# APM_BLE.net
KiCad netlist of a schematic drawn in EAGLE
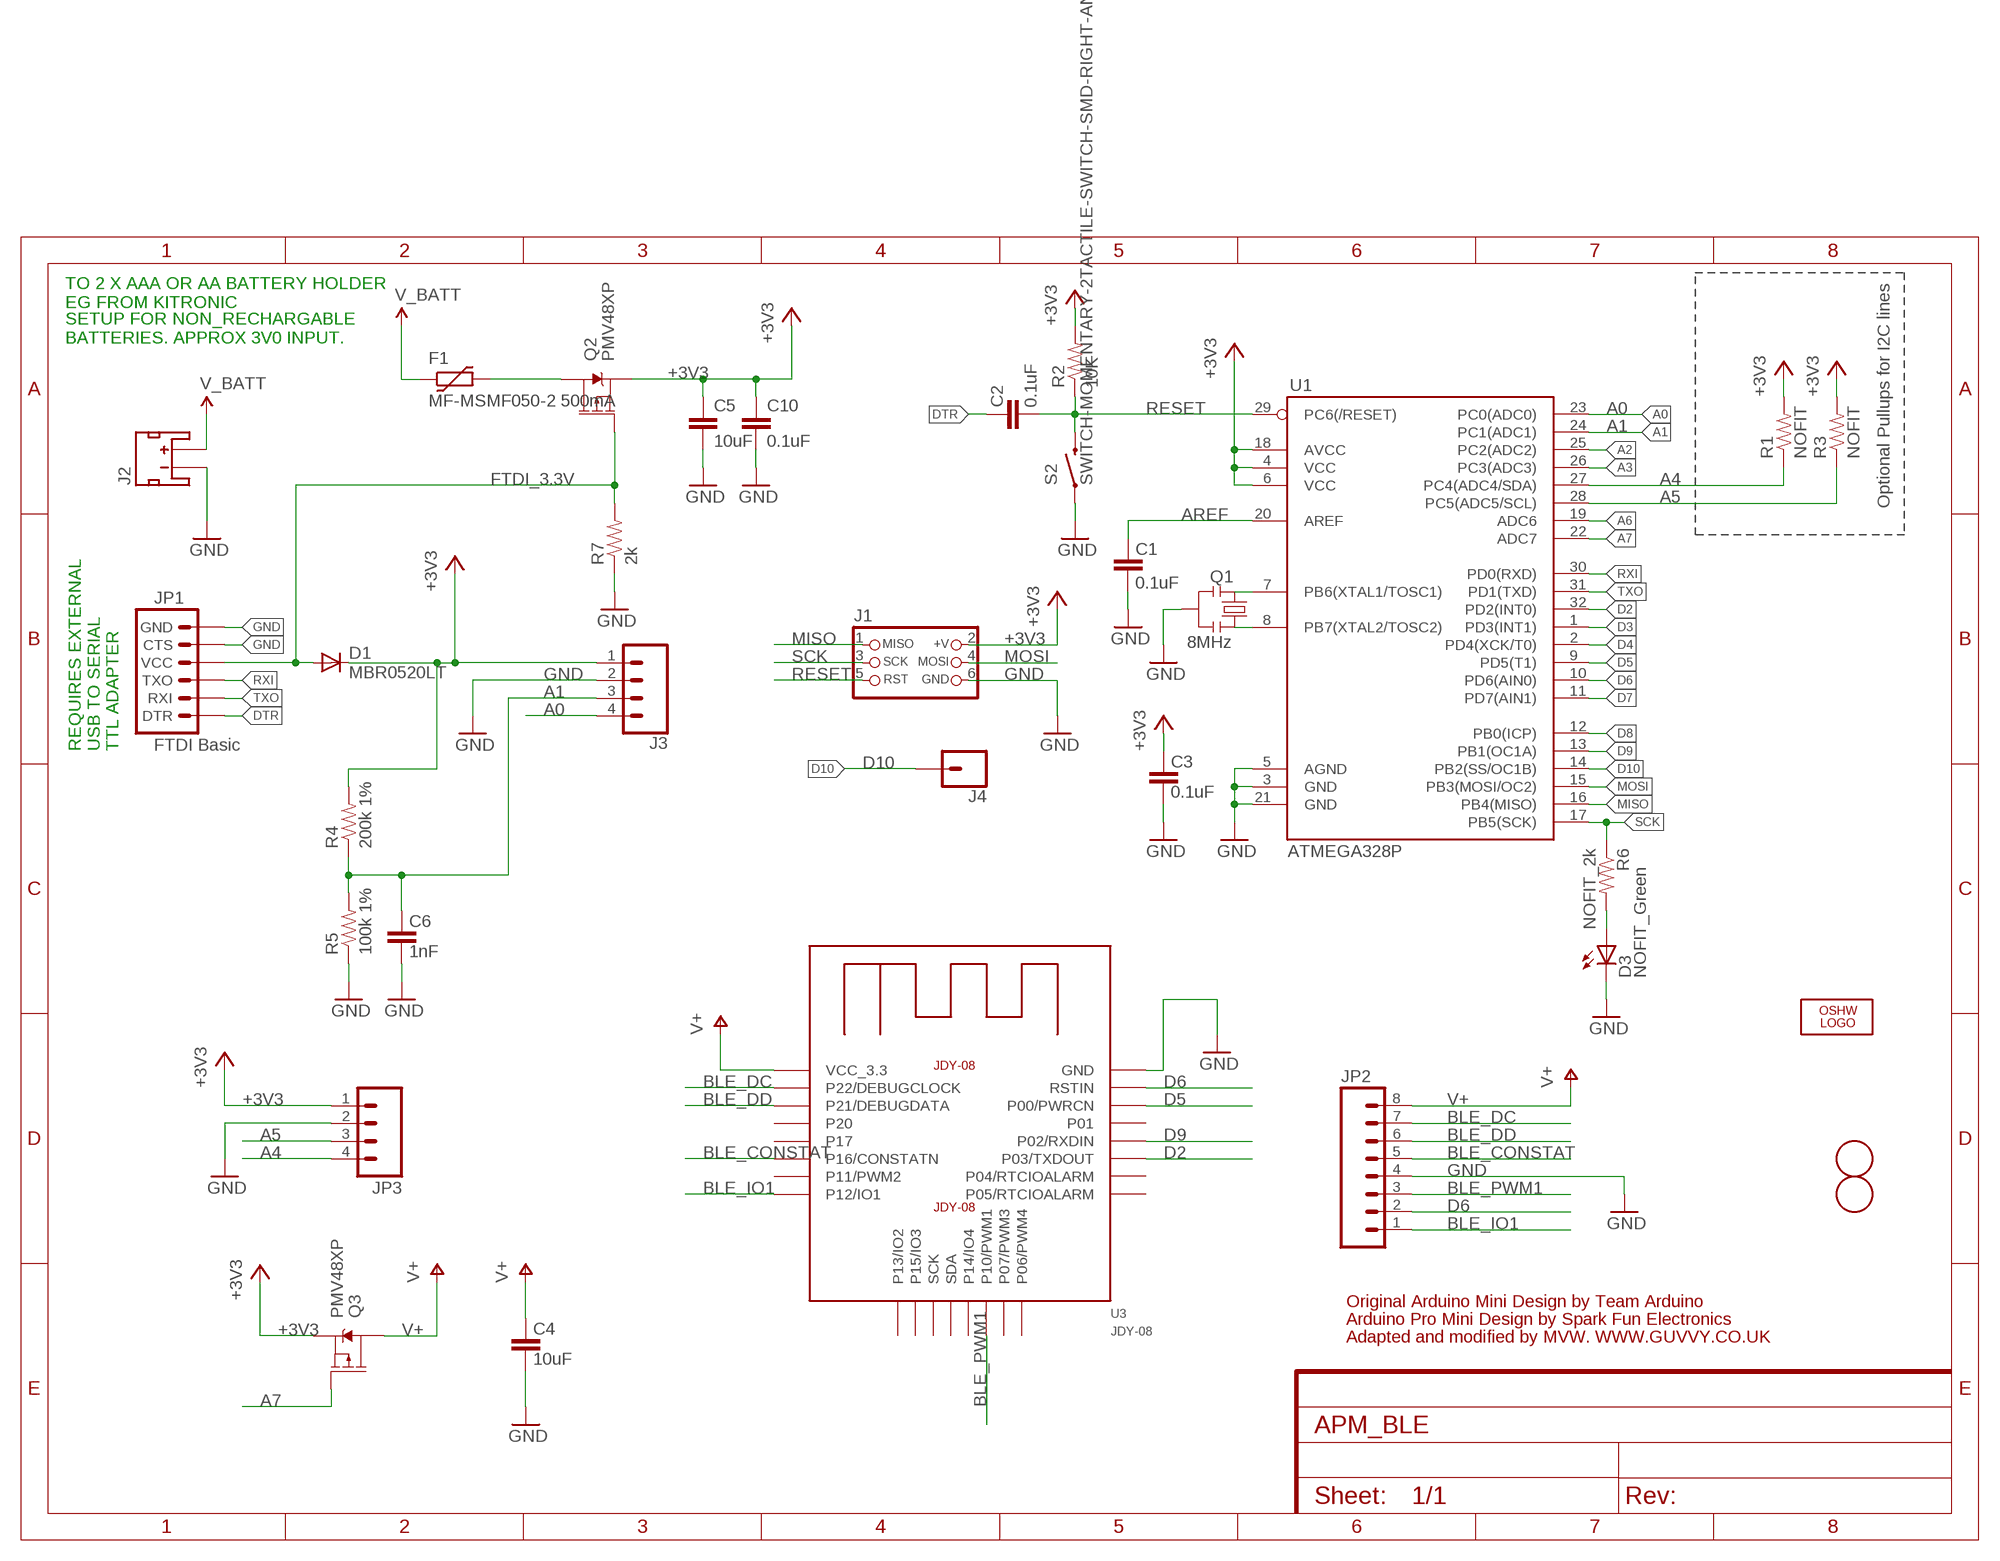
[diagram p0: schematic, sheet 1]

(export (version "E")
  (design (tool "Eeschema 10.0.6"))
  (components
    (comp (ref "C1")
      (value "0.1uF")
      (footprint "eagle-import:0603-CAP")
      (libsource (lib "eagle-import") (part "CAP0603-CAP"))
    )
    (comp (ref "C2")
      (value "0.1uF")
      (footprint "eagle-import:0603-CAP")
      (libsource (lib "eagle-import") (part "CAP0603-CAP"))
    )
    (comp (ref "C3")
      (value "0.1uF")
      (footprint "eagle-import:0603-CAP")
      (libsource (lib "eagle-import") (part "CAP0603-CAP"))
    )
    (comp (ref "C4")
      (value "10uF")
      (footprint "eagle-import:0603-CAP")
      (libsource (lib "eagle-import") (part "CAP0603-CAP"))
    )
    (comp (ref "C5")
      (value "10uF")
      (footprint "eagle-import:C0805K")
      (libsource (lib "eagle-import") (part "C-EUC0805K"))
    )
    (comp (ref "C6")
      (value "1nF")
      (footprint "eagle-import:0603-CAP")
      (libsource (lib "eagle-import") (part "CAP0603-CAP"))
    )
    (comp (ref "C10")
      (value "0.1uF")
      (footprint "eagle-import:0603-CAP")
      (libsource (lib "eagle-import") (part "CAP0603-CAP"))
    )
    (comp (ref "D1")
      (value "MBR0520LT")
      (footprint "eagle-import:SOD123")
      (libsource (lib "eagle-import") (part "MBR0520LT"))
    )
    (comp (ref "D3")
      (value "NOFIT_Green")
      (footprint "eagle-import:0603-LED-ALT1")
      (libsource (lib "eagle-import") (part "LED"))
    )
    (comp (ref "F1")
      (value "MF-MSMF050-2 500mA")
      (footprint "eagle-import:PTC1812L")
      (libsource (lib "eagle-import") (part "FUSE_PTC-1812"))
    )
    (comp (ref "FID1")
      (value "FIDUCIAL")
      (footprint "eagle-import:FIDUCIAL_1MM")
      (libsource (lib "eagle-import") (part "FIDUCIAL"))
    )
    (comp (ref "FID2")
      (value "FIDUCIAL")
      (footprint "eagle-import:FIDUCIAL_1MM")
      (libsource (lib "eagle-import") (part "FIDUCIAL"))
    )
    (comp (ref "J1")
      (value "CON_HEADER_PRG_AVR_ICSP-PTH")
      (footprint "eagle-import:HEADER_PRG_2X03")
      (libsource (lib "eagle-import") (part "CON_HEADER_PRG_AVR_ICSP-PTH"))
    )
    (comp (ref "J2")
      (value "B2B-PH-K-S(LF)(SN)")
      (footprint "eagle-import:JST-2-SMD")
      (libsource (lib "eagle-import") (part "JST_2MM_MALE"))
    )
    (comp (ref "J3")
      (value "CONN_04")
      (footprint "eagle-import:1X04")
      (libsource (lib "eagle-import") (part "CONN_04"))
    )
    (comp (ref "J4")
      (value "CONN_01")
      (footprint "eagle-import:1X01")
      (libsource (lib "eagle-import") (part "CONN_01"))
    )
    (comp (ref "JP1")
      (value "FTDI Basic")
      (footprint "eagle-import:1X06")
      (libsource (lib "eagle-import") (part "ARDUINO_SERIAL_PROGRAMPTH"))
    )
    (comp (ref "JP2")
      (value "M08BM08B-SRSS-TB")
      (footprint "eagle-import:BM08B-SRSS-TB")
      (libsource (lib "eagle-import") (part "M08BM08B-SRSS-TB"))
    )
    (comp (ref "JP3")
      (value "M04PTH")
      (footprint "eagle-import:1X04")
      (libsource (lib "eagle-import") (part "M04PTH"))
    )
    (comp (ref "LOGO1")
      (value "OSHW_LOGO_FILLX0200-NT")
      (footprint "eagle-import:OSHW_FILLX200_NOTEXT")
      (libsource (lib "eagle-import") (part "OSHW_LOGO_FILLX0200-NT"))
    )
    (comp (ref "Q1")
      (value "8MHz")
      (footprint "eagle-import:RESONATOR-SMD-1_1")
      (libsource (lib "eagle-import") (part "RESONATOR1{colon}1"))
    )
    (comp (ref "Q2")
      (value "PMV48XP")
      (footprint "eagle-import:SOT23-3")
      (libsource (lib "eagle-import") (part "MOSFET_PCH-IRLML2244"))
    )
    (comp (ref "Q3")
      (value "PMV48XP")
      (footprint "eagle-import:SOT23-3")
      (libsource (lib "eagle-import") (part "MOSFET_PCH-IRLML2244"))
    )
    (comp (ref "R1")
      (value "NOFIT")
      (footprint "eagle-import:0603-RES")
      (libsource (lib "eagle-import") (part "RESISTOR0603-RES"))
    )
    (comp (ref "R2")
      (value "10K")
      (footprint "eagle-import:0603-RES")
      (libsource (lib "eagle-import") (part "RESISTOR0603-RES"))
    )
    (comp (ref "R3")
      (value "NOFIT")
      (footprint "eagle-import:0603-RES")
      (libsource (lib "eagle-import") (part "RESISTOR0603-RES"))
    )
    (comp (ref "R4")
      (value "200k 1%")
      (footprint "eagle-import:0603-RES")
      (libsource (lib "eagle-import") (part "RESISTOR0603-RES"))
    )
    (comp (ref "R5")
      (value "100k 1%")
      (footprint "eagle-import:0603-RES")
      (libsource (lib "eagle-import") (part "RESISTOR0603-RES"))
    )
    (comp (ref "R6")
      (value "NOFIT_2k")
      (footprint "eagle-import:0603-RES")
      (libsource (lib "eagle-import") (part "RESISTOR0603-RES"))
    )
    (comp (ref "R7")
      (value "2k")
      (footprint "eagle-import:0603-RES")
      (libsource (lib "eagle-import") (part "RESISTOR0603-RES"))
    )
    (comp (ref "S2")
      (value "SWITCH-MOMENTARY-2TACTILE-SWITCH-SMD-RIGHT-ANGLE")
      (footprint "eagle-import:TACTILE_SWITCH-SMD-RIGHT-ANGLE")
      (libsource (lib "eagle-import") (part "SWITCH-MOMENTARY-2TACTILE-SWITCH-SMD-RIGHT-ANGLE"))
    )
    (comp (ref "U1")
      (value "ATMEGA328P")
      (footprint "eagle-import:TQFP32-08")
      (libsource (lib "eagle-import") (part "ATMEGA168"))
    )
    (comp (ref "U3")
      (value "JDY-08")
      (footprint "eagle-import:JDY-08")
      (libsource (lib "eagle-import") (part "JDY-08"))
    )
  )
  (nets
    (net (code "1") (name "+3V3") (class "Default")
      (node (ref "C10") (pin "1") (pinfunction "1_1") (pintype "passive"))
      (node (ref "C3") (pin "2") (pinfunction "2_2") (pintype "passive"))
      (node (ref "C5") (pin "1") (pinfunction "1_1") (pintype "passive"))
      (node (ref "D1") (pin "C") (pinfunction "C_C") (pintype "passive"))
      (node (ref "J1") (pin "2") (pinfunction "+V_2") (pintype "passive"))
      (node (ref "J3") (pin "1") (pinfunction "1_1") (pintype "passive"))
      (node (ref "JP3") (pin "1") (pinfunction "1_1") (pintype "passive"))
      (node (ref "Q2") (pin "2") (pinfunction "S_2") (pintype "bidirectional"))
      (node (ref "Q3") (pin "2") (pinfunction "S_2") (pintype "bidirectional"))
      (node (ref "R1") (pin "2") (pinfunction "2_2") (pintype "passive"))
      (node (ref "R2") (pin "2") (pinfunction "2_2") (pintype "passive"))
      (node (ref "R3") (pin "2") (pinfunction "2_2") (pintype "passive"))
      (node (ref "R4") (pin "2") (pinfunction "2_2") (pintype "passive"))
      (node (ref "U1") (pin "18") (pinfunction "AVCC_18") (pintype "bidirectional"))
      (node (ref "U1") (pin "4") (pinfunction "VCC_4") (pintype "bidirectional"))
      (node (ref "U1") (pin "6") (pinfunction "VCC_6") (pintype "bidirectional"))
    )
    (net (code "2") (name "/A4") (class "Default")
      (node (ref "JP3") (pin "4") (pinfunction "4_4") (pintype "passive"))
      (node (ref "R1") (pin "1") (pinfunction "1_1") (pintype "passive"))
      (node (ref "U1") (pin "27") (pinfunction "PC4(ADC4/SDA)_27") (pintype "bidirectional"))
    )
    (net (code "3") (name "/A5") (class "Default")
      (node (ref "JP3") (pin "3") (pinfunction "3_3") (pintype "passive"))
      (node (ref "R3") (pin "1") (pinfunction "1_1") (pintype "passive"))
      (node (ref "U1") (pin "28") (pinfunction "PC5(ADC5/SCL)_28") (pintype "bidirectional"))
    )
    (net (code "4") (name "/AREF") (class "Default")
      (node (ref "C1") (pin "2") (pinfunction "2_2") (pintype "passive"))
      (node (ref "U1") (pin "20") (pinfunction "AREF_20") (pintype "bidirectional"))
    )
    (net (code "5") (name "/BLE_CONSTAT") (class "Default")
      (node (ref "JP2") (pin "5") (pinfunction "5_5") (pintype "passive"))
      (node (ref "U3") (pin "P16/CONSTATN") (pinfunction "P16/CONSTATN_P16/CONSTATN") (pintype "bidirectional"))
    )
    (net (code "6") (name "/BLE_DC") (class "Default")
      (node (ref "JP2") (pin "7") (pinfunction "7_7") (pintype "passive"))
      (node (ref "U3") (pin "P22/DEBUGCLOCK") (pinfunction "P22/DEBUGCLOCK_P22/DEBUGCLOCK") (pintype "bidirectional"))
    )
    (net (code "7") (name "/BLE_DD") (class "Default")
      (node (ref "JP2") (pin "6") (pinfunction "6_6") (pintype "passive"))
      (node (ref "U3") (pin "P21/DEBUGDATA") (pinfunction "P21/DEBUGDATA_P21/DEBUGDATA") (pintype "bidirectional"))
    )
    (net (code "8") (name "/BLE_IO1") (class "Default")
      (node (ref "JP2") (pin "1") (pinfunction "1_1") (pintype "passive"))
      (node (ref "U3") (pin "P12/IO1") (pinfunction "P12/IO1_P12/IO1") (pintype "bidirectional"))
    )
    (net (code "9") (name "/BLE_PWM1") (class "Default")
      (node (ref "JP2") (pin "3") (pinfunction "3_3") (pintype "passive"))
      (node (ref "U3") (pin "P10/PWM1") (pinfunction "P10/PWM1_P10/PWM1") (pintype "bidirectional"))
    )
    (net (code "10") (name "/FTDI_3.3V") (class "Default")
      (node (ref "D1") (pin "A") (pinfunction "A_A") (pintype "passive"))
      (node (ref "JP1") (pin "4") (pinfunction "VCC_4") (pintype "passive"))
      (node (ref "Q2") (pin "1") (pinfunction "G_1") (pintype "bidirectional"))
      (node (ref "R7") (pin "2") (pinfunction "2_2") (pintype "passive"))
    )
    (net (code "11") (name "/RESET") (class "Default")
      (node (ref "C2") (pin "1") (pinfunction "1_1") (pintype "passive"))
      (node (ref "J1") (pin "5") (pinfunction "RST_5") (pintype "passive"))
      (node (ref "R2") (pin "1") (pinfunction "1_1") (pintype "passive"))
      (node (ref "S2") (pin "2") (pinfunction "2_2") (pintype "passive"))
      (node (ref "U1") (pin "29") (pinfunction "PC6(/RESET)_29") (pintype "bidirectional"))
    )
    (net (code "12") (name "A0") (class "Default")
      (node (ref "J3") (pin "4") (pinfunction "4_4") (pintype "passive"))
      (node (ref "U1") (pin "23") (pinfunction "PC0(ADC0)_23") (pintype "bidirectional"))
    )
    (net (code "13") (name "A1") (class "Default")
      (node (ref "C6") (pin "2") (pinfunction "2_2") (pintype "passive"))
      (node (ref "J3") (pin "3") (pinfunction "3_3") (pintype "passive"))
      (node (ref "R4") (pin "1") (pinfunction "1_1") (pintype "passive"))
      (node (ref "R5") (pin "2") (pinfunction "2_2") (pintype "passive"))
      (node (ref "U1") (pin "24") (pinfunction "PC1(ADC1)_24") (pintype "bidirectional"))
    )
    (net (code "14") (name "A2") (class "Default")
      (node (ref "U1") (pin "25") (pinfunction "PC2(ADC2)_25") (pintype "bidirectional"))
    )
    (net (code "15") (name "A3") (class "Default")
      (node (ref "U1") (pin "26") (pinfunction "PC3(ADC3)_26") (pintype "bidirectional"))
    )
    (net (code "16") (name "A6") (class "Default")
      (node (ref "U1") (pin "19") (pinfunction "ADC6_19") (pintype "bidirectional"))
    )
    (net (code "17") (name "A7") (class "Default")
      (node (ref "Q3") (pin "1") (pinfunction "G_1") (pintype "bidirectional"))
      (node (ref "U1") (pin "22") (pinfunction "ADC7_22") (pintype "bidirectional"))
    )
    (net (code "18") (name "D2") (class "Default")
      (node (ref "U1") (pin "32") (pinfunction "PD2(INT0)_32") (pintype "bidirectional"))
      (node (ref "U3") (pin "P03/TXDOUT") (pinfunction "P03/TXDOUT_P03/TXDOUT") (pintype "bidirectional"))
    )
    (net (code "19") (name "D3") (class "Default")
      (node (ref "U1") (pin "1") (pinfunction "PD3(INT1)_1") (pintype "bidirectional"))
    )
    (net (code "20") (name "D4") (class "Default")
      (node (ref "U1") (pin "2") (pinfunction "PD4(XCK/T0)_2") (pintype "bidirectional"))
    )
    (net (code "21") (name "D5") (class "Default")
      (node (ref "U1") (pin "9") (pinfunction "PD5(T1)_9") (pintype "bidirectional"))
      (node (ref "U3") (pin "P00/PWRCN") (pinfunction "P00/PWRCN_P00/PWRCN") (pintype "bidirectional"))
    )
    (net (code "22") (name "D6") (class "Default")
      (node (ref "JP2") (pin "2") (pinfunction "2_2") (pintype "passive"))
      (node (ref "U1") (pin "10") (pinfunction "PD6(AIN0)_10") (pintype "bidirectional"))
      (node (ref "U3") (pin "RSTIN") (pinfunction "RSTIN_RSTIN") (pintype "bidirectional"))
    )
    (net (code "23") (name "D7") (class "Default")
      (node (ref "U1") (pin "11") (pinfunction "PD7(AIN1)_11") (pintype "bidirectional"))
    )
    (net (code "24") (name "D8") (class "Default")
      (node (ref "U1") (pin "12") (pinfunction "PB0(ICP)_12") (pintype "bidirectional"))
    )
    (net (code "25") (name "D9") (class "Default")
      (node (ref "U1") (pin "13") (pinfunction "PB1(OC1A)_13") (pintype "bidirectional"))
      (node (ref "U3") (pin "P02/RXDIN") (pinfunction "P02/RXDIN_P02/RXDIN") (pintype "bidirectional"))
    )
    (net (code "26") (name "D10") (class "Default")
      (node (ref "J4") (pin "1") (pinfunction "1_1") (pintype "passive"))
      (node (ref "U1") (pin "14") (pinfunction "PB2(SS/OC1B)_14") (pintype "bidirectional"))
    )
    (net (code "27") (name "DTR") (class "Default")
      (node (ref "C2") (pin "2") (pinfunction "2_2") (pintype "passive"))
      (node (ref "JP1") (pin "1") (pinfunction "DTR_1") (pintype "passive"))
    )
    (net (code "28") (name "GND") (class "Default")
      (node (ref "C1") (pin "1") (pinfunction "1_1") (pintype "passive"))
      (node (ref "C10") (pin "2") (pinfunction "2_2") (pintype "passive"))
      (node (ref "C3") (pin "1") (pinfunction "1_1") (pintype "passive"))
      (node (ref "C4") (pin "1") (pinfunction "1_1") (pintype "passive"))
      (node (ref "C5") (pin "2") (pinfunction "2_2") (pintype "passive"))
      (node (ref "C6") (pin "1") (pinfunction "1_1") (pintype "passive"))
      (node (ref "D3") (pin "C") (pinfunction "C_C") (pintype "passive"))
      (node (ref "J1") (pin "6") (pinfunction "GND_6") (pintype "passive"))
      (node (ref "J2") (pin "1") (pinfunction "-_1") (pintype "bidirectional"))
      (node (ref "J3") (pin "2") (pinfunction "2_2") (pintype "passive"))
      (node (ref "JP1") (pin "5") (pinfunction "CTS_5") (pintype "passive"))
      (node (ref "JP1") (pin "6") (pinfunction "GND_6") (pintype "passive"))
      (node (ref "JP2") (pin "4") (pinfunction "4_4") (pintype "passive"))
      (node (ref "JP3") (pin "2") (pinfunction "2_2") (pintype "passive"))
      (node (ref "Q1") (pin "2") (pinfunction "2_2") (pintype "passive"))
      (node (ref "R5") (pin "1") (pinfunction "1_1") (pintype "passive"))
      (node (ref "R7") (pin "1") (pinfunction "1_1") (pintype "passive"))
      (node (ref "S2") (pin "1") (pinfunction "1_1") (pintype "passive"))
      (node (ref "U1") (pin "21") (pinfunction "GND_21") (pintype "bidirectional"))
      (node (ref "U1") (pin "3") (pinfunction "GND_3") (pintype "bidirectional"))
      (node (ref "U1") (pin "5") (pinfunction "AGND_5") (pintype "bidirectional"))
      (node (ref "U3") (pin "GND") (pinfunction "GND_GND") (pintype "bidirectional"))
    )
    (net (code "29") (name "MISO") (class "Default")
      (node (ref "J1") (pin "1") (pinfunction "MISO_1") (pintype "passive"))
      (node (ref "U1") (pin "16") (pinfunction "PB4(MISO)_16") (pintype "bidirectional"))
    )
    (net (code "30") (name "MOSI") (class "Default")
      (node (ref "J1") (pin "4") (pinfunction "MOSI_4") (pintype "passive"))
      (node (ref "U1") (pin "15") (pinfunction "PB3(MOSI/OC2)_15") (pintype "bidirectional"))
    )
    (net (code "31") (name "Net-(D3-PadA)") (class "Default")
      (node (ref "D3") (pin "A") (pinfunction "A_A") (pintype "passive"))
      (node (ref "R6") (pin "2") (pinfunction "2_2") (pintype "passive"))
    )
    (net (code "32") (name "Net-(Q2-D)") (class "Default")
      (node (ref "F1") (pin "2") (pinfunction "2_2") (pintype "passive"))
      (node (ref "Q2") (pin "3") (pinfunction "D_3") (pintype "bidirectional"))
    )
    (net (code "33") (name "Net-(U1-PB6(XTAL1{slash}TOSC1))") (class "Default")
      (node (ref "Q1") (pin "1") (pinfunction "1_1") (pintype "passive"))
      (node (ref "U1") (pin "7") (pinfunction "PB6(XTAL1/TOSC1)_7") (pintype "bidirectional"))
    )
    (net (code "34") (name "Net-(U1-PB7(XTAL2{slash}TOSC2))") (class "Default")
      (node (ref "Q1") (pin "3") (pinfunction "3_3") (pintype "passive"))
      (node (ref "U1") (pin "8") (pinfunction "PB7(XTAL2/TOSC2)_8") (pintype "bidirectional"))
    )
    (net (code "35") (name "RXI") (class "Default")
      (node (ref "JP1") (pin "3") (pinfunction "TXO_3") (pintype "passive"))
      (node (ref "U1") (pin "30") (pinfunction "PD0(RXD)_30") (pintype "bidirectional"))
    )
    (net (code "36") (name "SCK") (class "Default")
      (node (ref "J1") (pin "3") (pinfunction "SCK_3") (pintype "passive"))
      (node (ref "R6") (pin "1") (pinfunction "1_1") (pintype "passive"))
      (node (ref "U1") (pin "17") (pinfunction "PB5(SCK)_17") (pintype "bidirectional"))
    )
    (net (code "37") (name "TXO") (class "Default")
      (node (ref "JP1") (pin "2") (pinfunction "RXI_2") (pintype "passive"))
      (node (ref "U1") (pin "31") (pinfunction "PD1(TXD)_31") (pintype "bidirectional"))
    )
    (net (code "38") (name "V+") (class "Default")
      (node (ref "C4") (pin "2") (pinfunction "2_2") (pintype "passive"))
      (node (ref "JP2") (pin "8") (pinfunction "8_8") (pintype "passive"))
      (node (ref "Q3") (pin "3") (pinfunction "D_3") (pintype "bidirectional"))
      (node (ref "U3") (pin "VCC_3.3") (pinfunction "VCC_3.3_VCC_3.3") (pintype "bidirectional"))
    )
    (net (code "39") (name "V_BATT") (class "Default")
      (node (ref "F1") (pin "1") (pinfunction "1_1") (pintype "passive"))
      (node (ref "J2") (pin "2") (pinfunction "+_2") (pintype "bidirectional"))
    )
    (net (code "40") (name "unconnected-(J2-PAD1-PadNC1)") (class "Default")
      (node (ref "J2") (pin "NC1") (pinfunction "PAD1_NC1") (pintype "bidirectional"))
    )
    (net (code "41") (name "unconnected-(J2-PAD2-PadNC2)") (class "Default")
      (node (ref "J2") (pin "NC2") (pinfunction "PAD2_NC2") (pintype "bidirectional"))
    )
    (net (code "42") (name "unconnected-(U3-P04{slash}RTCIOALARM-PadP04{slash}RTCALARMIO)") (class "Default")
      (node (ref "U3") (pin "P04/RTCALARMIO") (pinfunction "P04/RTCIOALARM_P04/RTCALARMIO") (pintype "bidirectional"))
    )
    (net (code "43") (name "unconnected-(U3-P05{slash}RTCIOALARM-PadP05{slash}RTCALARMIO)") (class "Default")
      (node (ref "U3") (pin "P05/RTCALARMIO") (pinfunction "P05/RTCIOALARM_P05/RTCALARMIO") (pintype "bidirectional"))
    )
    (net (code "44") (name "unconnected-(U3-PadP01)") (class "Default")
      (node (ref "U3") (pin "P01") (pinfunction "P01_P01") (pintype "bidirectional"))
    )
    (net (code "45") (name "unconnected-(U3-PadP06{slash}PWM4)") (class "Default")
      (node (ref "U3") (pin "P06/PWM4") (pinfunction "P06/PWM4_P06/PWM4") (pintype "bidirectional"))
    )
    (net (code "46") (name "unconnected-(U3-PadP07{slash}PWM3)") (class "Default")
      (node (ref "U3") (pin "P07/PWM3") (pinfunction "P07/PWM3_P07/PWM3") (pintype "bidirectional"))
    )
    (net (code "47") (name "unconnected-(U3-PadP11{slash}PWM2)") (class "Default")
      (node (ref "U3") (pin "P11/PWM2") (pinfunction "P11/PWM2_P11/PWM2") (pintype "bidirectional"))
    )
    (net (code "48") (name "unconnected-(U3-PadP13{slash}IO2)") (class "Default")
      (node (ref "U3") (pin "P13/IO2") (pinfunction "P13/IO2_P13/IO2") (pintype "bidirectional"))
    )
    (net (code "49") (name "unconnected-(U3-PadP14{slash}IO4)") (class "Default")
      (node (ref "U3") (pin "P14/IO4") (pinfunction "P14/IO4_P14/IO4") (pintype "bidirectional"))
    )
    (net (code "50") (name "unconnected-(U3-PadP15{slash}IO3)") (class "Default")
      (node (ref "U3") (pin "P15/IO3") (pinfunction "P15/IO3_P15/IO3") (pintype "bidirectional"))
    )
    (net (code "51") (name "unconnected-(U3-PadP17)") (class "Default")
      (node (ref "U3") (pin "P17") (pinfunction "P17_P17") (pintype "bidirectional"))
    )
    (net (code "52") (name "unconnected-(U3-PadP20)") (class "Default")
      (node (ref "U3") (pin "P20") (pinfunction "P20_P20") (pintype "bidirectional"))
    )
    (net (code "53") (name "unconnected-(U3-PadSCK)") (class "Default")
      (node (ref "U3") (pin "SCK") (pinfunction "SCK_SCK") (pintype "bidirectional"))
    )
    (net (code "54") (name "unconnected-(U3-PadSDA)") (class "Default")
      (node (ref "U3") (pin "SDA") (pinfunction "SDA_SDA") (pintype "bidirectional"))
    )
  )
)
